# ESP32_with_USBC.net
KiCad netlist of a schematic drawn in Altium Designer
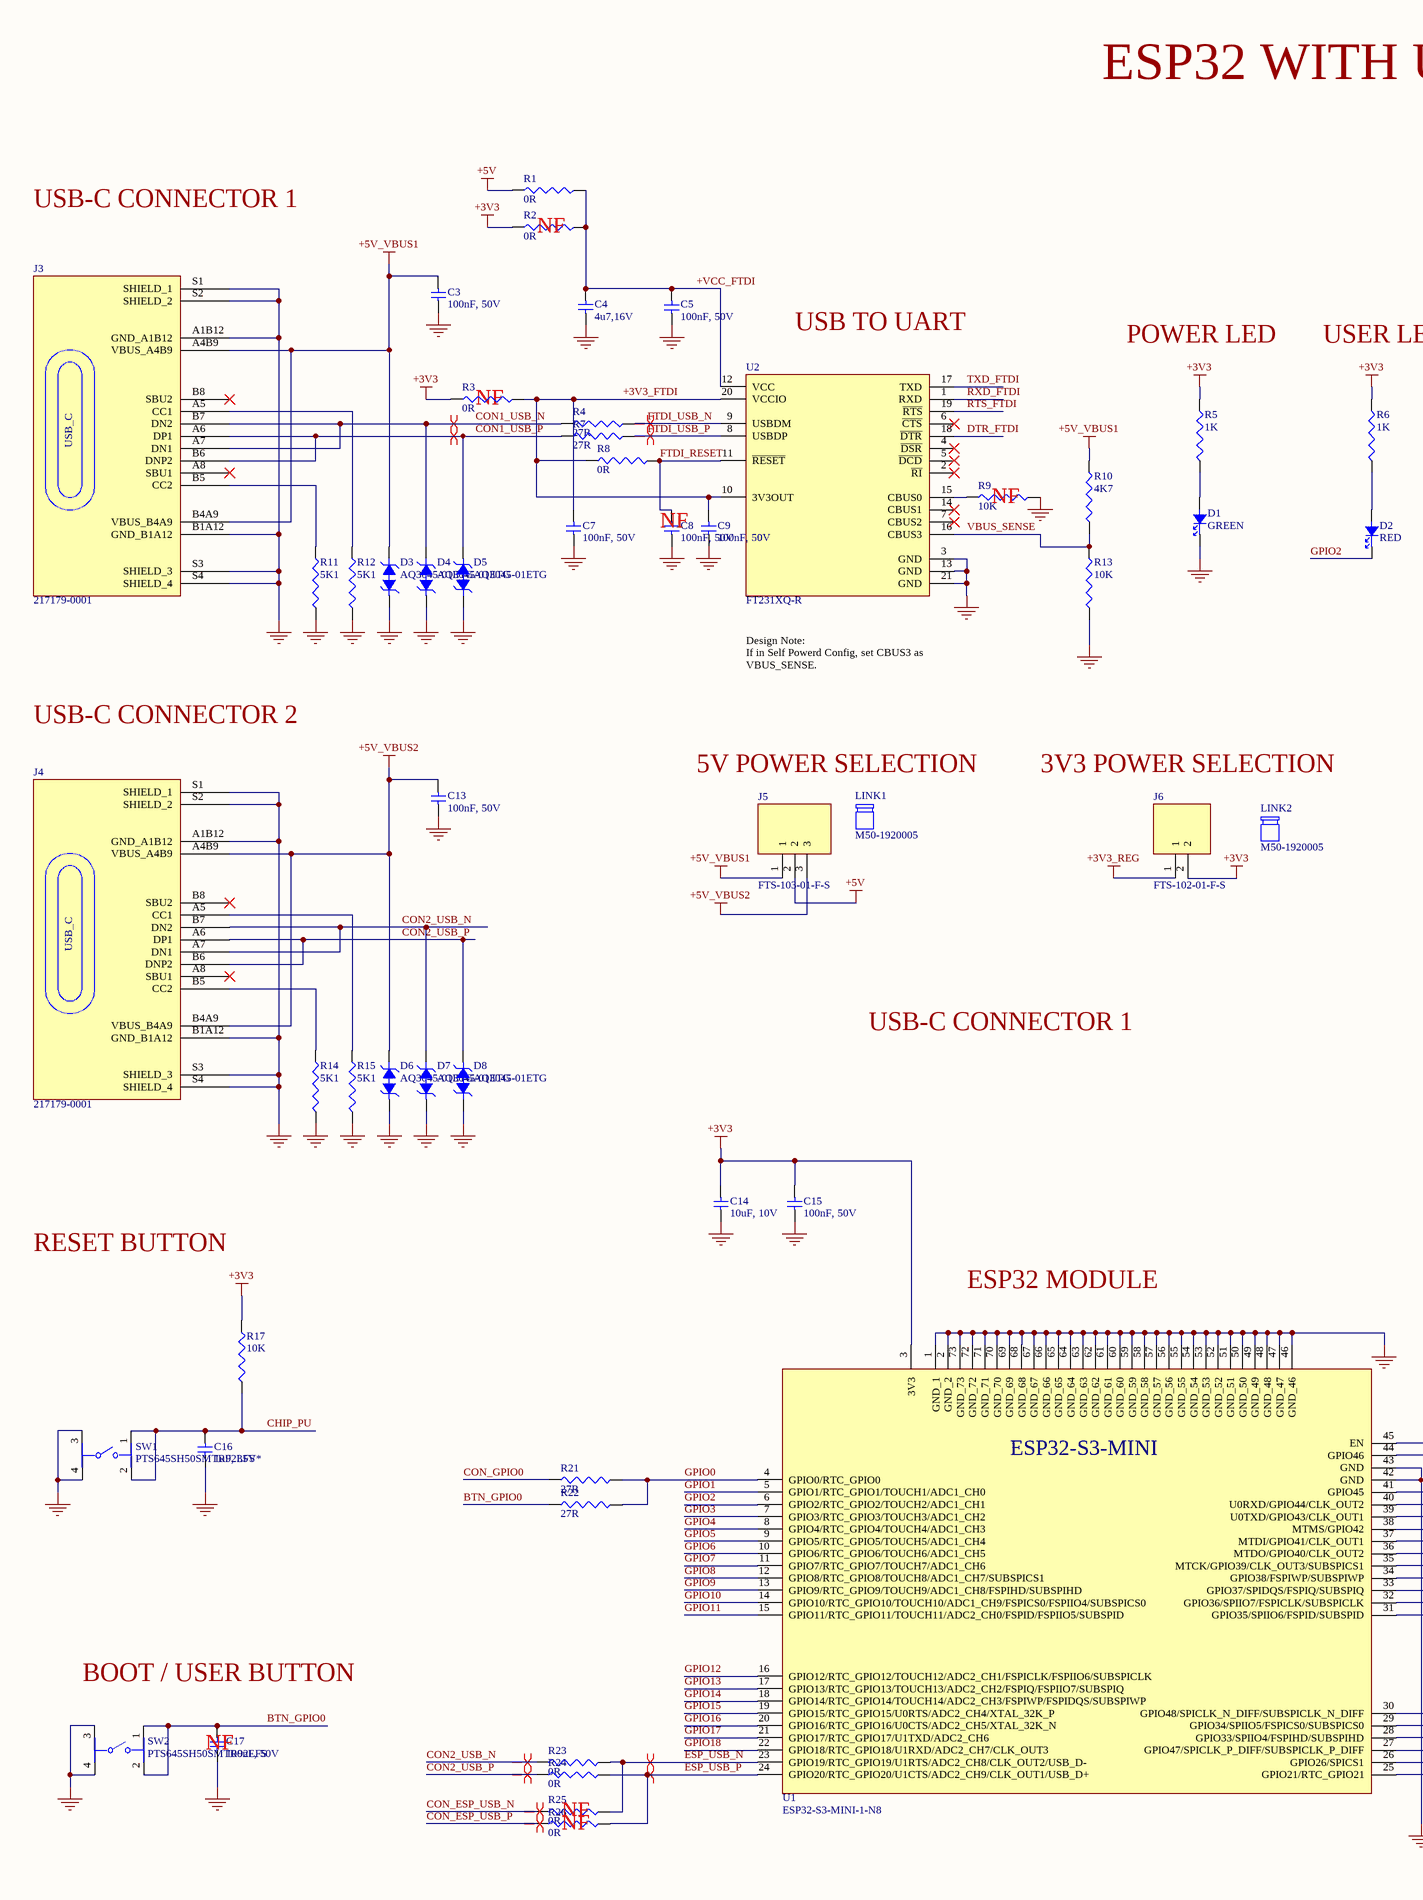
[diagram p0: ESP32 with USBC.SchDoc, left]
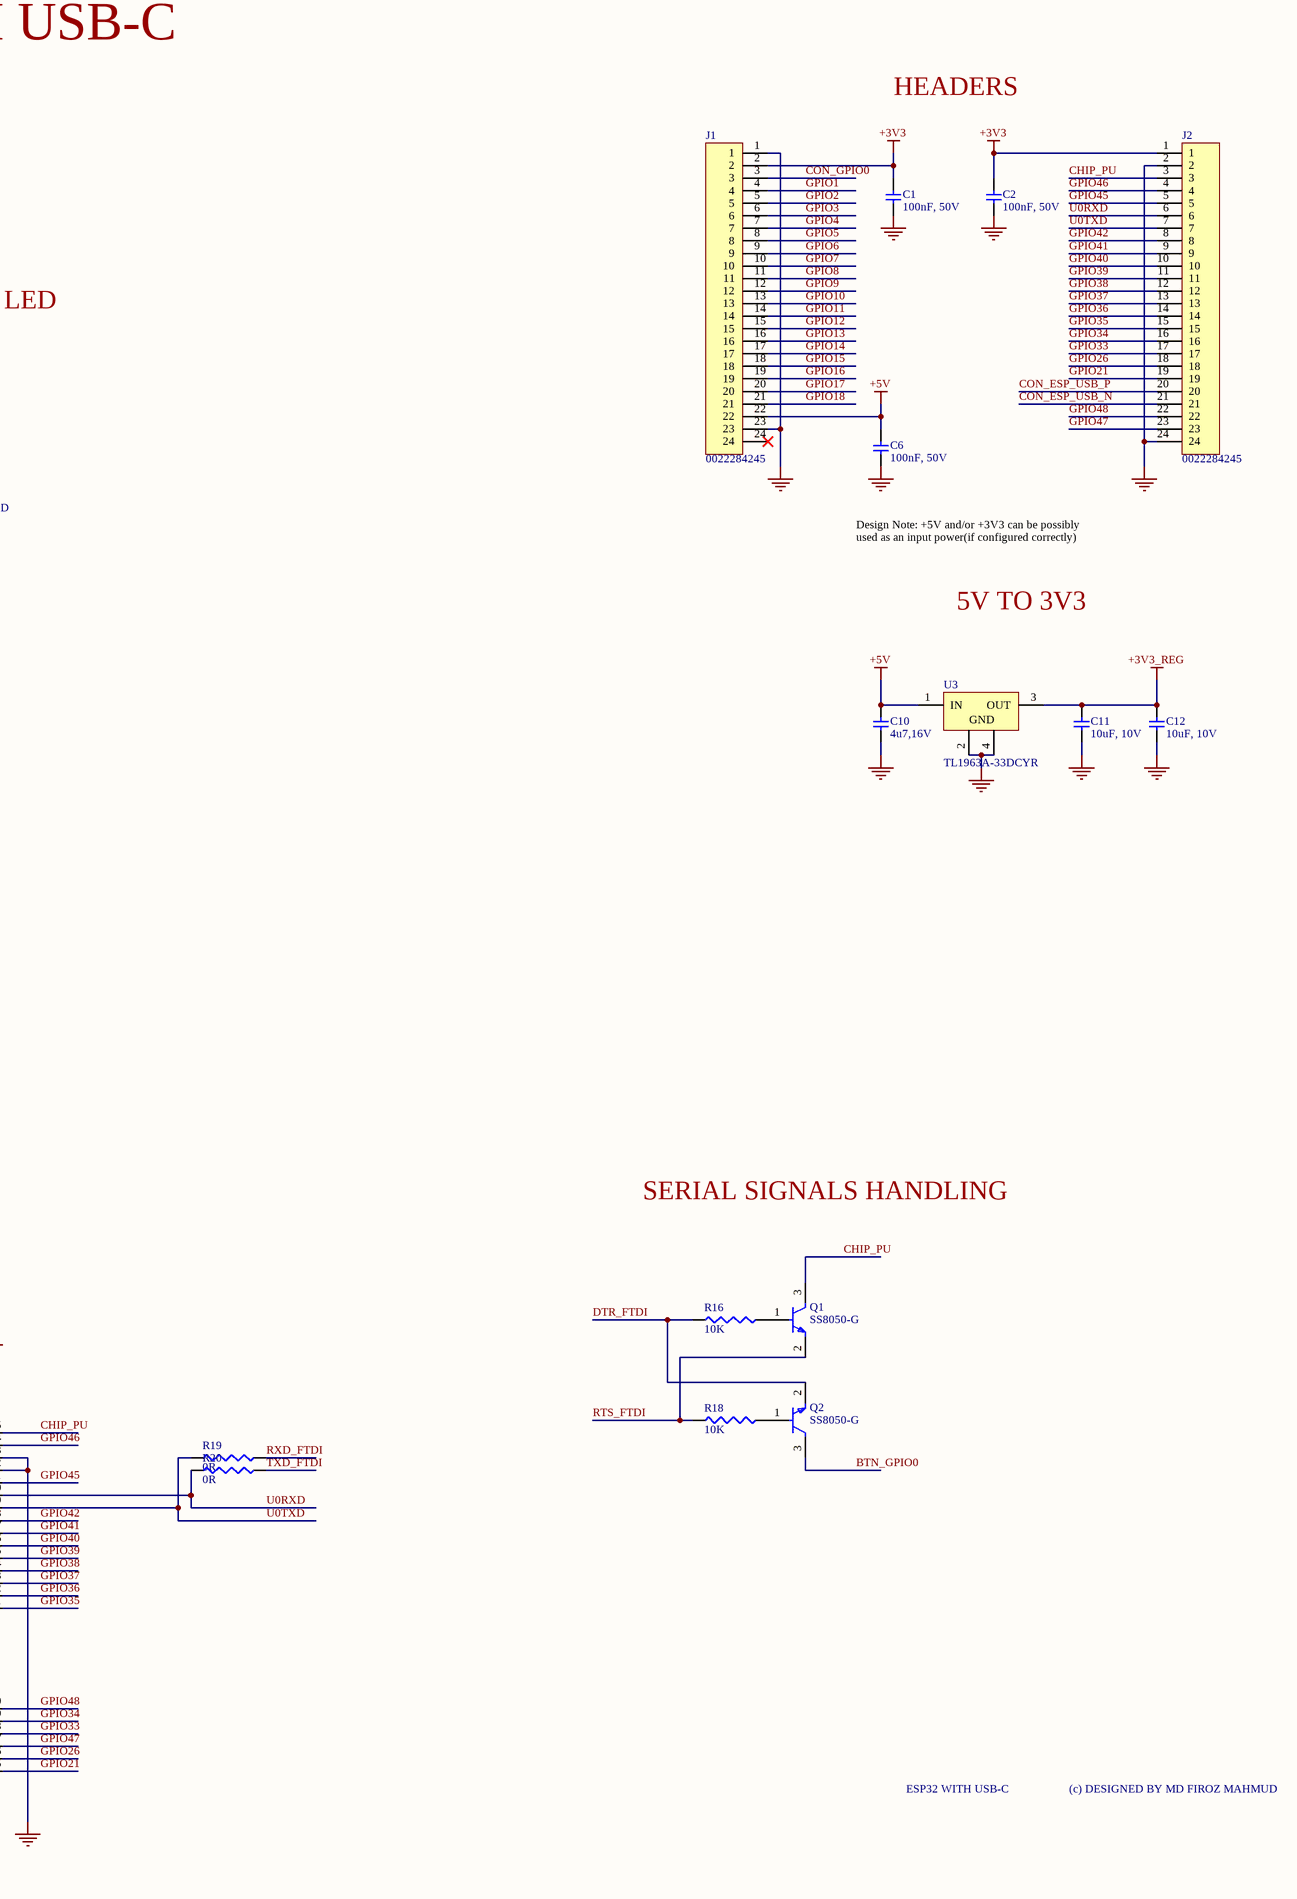
[diagram p1: ESP32 with USBC.SchDoc, right]

(export (version "E")
  (design (tool "Eeschema 10.0.6"))
  (components
    (comp (ref "C1")
      (value "100nF, 50V")
      (footprint "CAPC1005X55N")
      (description "CAP CER 0.1UF 50V X7R 0402")
      (fields
        (field (name "MANUFACTURER") "Samsung")
        (field (name "MANUFACTURER PART NUMBER") "CL05B104KB54PNC")
      )
      (libsource (lib "Schlib") (part "CL05B104KB54PNC"))
    )
    (comp (ref "C2")
      (value "100nF, 50V")
      (footprint "CAPC1005X55N")
      (description "CAP CER 0.1UF 50V X7R 0402")
      (fields
        (field (name "MANUFACTURER") "Samsung")
        (field (name "MANUFACTURER PART NUMBER") "CL05B104KB54PNC")
      )
      (libsource (lib "Schlib") (part "CL05B104KB54PNC"))
    )
    (comp (ref "C3")
      (value "100nF, 50V")
      (footprint "CAPC1005X55N")
      (description "CAP CER 0.1UF 50V X7R 0402")
      (fields
        (field (name "MANUFACTURER") "Samsung")
        (field (name "MANUFACTURER PART NUMBER") "CL05B104KB54PNC")
      )
      (libsource (lib "Schlib") (part "CL05B104KB54PNC"))
    )
    (comp (ref "C4")
      (value "4u7,16V")
      (footprint "CAPC1005X55N")
      (description "CAP CER 4.7UF 16V X5R 0402")
      (fields
        (field (name "MANUFACTURER") "Samsung")
        (field (name "MANUFACTURER PART NUMBER") "CL05A475MO5NUNC")
      )
      (libsource (lib "Schlib") (part "CL05A475MO5NUNC"))
    )
    (comp (ref "C5")
      (value "100nF, 50V")
      (footprint "CAPC1005X55N")
      (description "CAP CER 0.1UF 50V X7R 0402")
      (fields
        (field (name "MANUFACTURER") "Samsung")
        (field (name "MANUFACTURER PART NUMBER") "CL05B104KB54PNC")
      )
      (libsource (lib "Schlib") (part "CL05B104KB54PNC"))
    )
    (comp (ref "C6")
      (value "100nF, 50V")
      (footprint "CAPC1005X55N")
      (description "CAP CER 0.1UF 50V X7R 0402")
      (fields
        (field (name "MANUFACTURER") "Samsung")
        (field (name "MANUFACTURER PART NUMBER") "CL05B104KB54PNC")
      )
      (libsource (lib "Schlib") (part "CL05B104KB54PNC"))
    )
    (comp (ref "C7")
      (value "100nF, 50V")
      (footprint "CAPC1005X55N")
      (description "CAP CER 0.1UF 50V X7R 0402")
      (fields
        (field (name "MANUFACTURER") "Samsung")
        (field (name "MANUFACTURER PART NUMBER") "CL05B104KB54PNC")
      )
      (libsource (lib "Schlib") (part "CL05B104KB54PNC"))
    )
    (comp (ref "C8")
      (value "100nF, 50V")
      (footprint "CAPC1005X55N")
      (description "CAP CER 0.1UF 50V X7R 0402")
      (fields
        (field (name "MANUFACTURER") "Samsung")
        (field (name "MANUFACTURER PART NUMBER") "CL05B104KB54PNC")
      )
      (libsource (lib "Schlib") (part "CL05B104KB54PNC"))
    )
    (comp (ref "C9")
      (value "100nF, 50V")
      (footprint "CAPC1005X55N")
      (description "CAP CER 0.1UF 50V X7R 0402")
      (fields
        (field (name "MANUFACTURER") "Samsung")
        (field (name "MANUFACTURER PART NUMBER") "CL05B104KB54PNC")
      )
      (libsource (lib "Schlib") (part "CL05B104KB54PNC"))
    )
    (comp (ref "C10")
      (value "4u7,16V")
      (footprint "CAPC1005X55N")
      (description "CAP CER 4.7UF 16V X5R 0402")
      (fields
        (field (name "MANUFACTURER") "Samsung")
        (field (name "MANUFACTURER PART NUMBER") "CL05A475MO5NUNC")
      )
      (libsource (lib "Schlib") (part "CL05A475MO5NUNC"))
    )
    (comp (ref "C11")
      (value "10uF, 10V")
      (footprint "CAPC1005X55N")
      (description "CAP CER 10UF 10V X5R 0402")
      (fields
        (field (name "MANUFACTURER") "Samsung")
        (field (name "MANUFACTURER PART NUMBER") "CL05A106MP8NUB8")
      )
      (libsource (lib "Schlib") (part "CL05A106MP8NUB8"))
    )
    (comp (ref "C12")
      (value "10uF, 10V")
      (footprint "CAPC1005X55N")
      (description "CAP CER 10UF 10V X5R 0402")
      (fields
        (field (name "MANUFACTURER") "Samsung")
        (field (name "MANUFACTURER PART NUMBER") "CL05A106MP8NUB8")
      )
      (libsource (lib "Schlib") (part "CL05A106MP8NUB8"))
    )
    (comp (ref "C13")
      (value "100nF, 50V")
      (footprint "CAPC1005X55N")
      (description "CAP CER 0.1UF 50V X7R 0402")
      (fields
        (field (name "MANUFACTURER") "Samsung")
        (field (name "MANUFACTURER PART NUMBER") "CL05B104KB54PNC")
      )
      (libsource (lib "Schlib") (part "CL05B104KB54PNC"))
    )
    (comp (ref "C14")
      (value "10uF, 10V")
      (footprint "CAPC1005X55N")
      (description "CAP CER 10UF 10V X5R 0402")
      (fields
        (field (name "MANUFACTURER") "Samsung")
        (field (name "MANUFACTURER PART NUMBER") "CL05A106MP8NUB8")
      )
      (libsource (lib "Schlib") (part "CL05A106MP8NUB8"))
    )
    (comp (ref "C15")
      (value "100nF, 50V")
      (footprint "CAPC1005X55N")
      (description "CAP CER 0.1UF 50V X7R 0402")
      (fields
        (field (name "MANUFACTURER") "Samsung")
        (field (name "MANUFACTURER PART NUMBER") "CL05B104KB54PNC")
      )
      (libsource (lib "Schlib") (part "CL05B104KB54PNC"))
    )
    (comp (ref "C16")
      (value "1uF, 35V*")
      (footprint "CAPC1005X55N")
      (description "CAP CER 1UF 35V X5R 0402")
      (fields
        (field (name "MANUFACTURER") "Samsung")
        (field (name "MANUFACTURER PART NUMBER") "CL05A105KL5NRNC")
      )
      (libsource (lib "Schlib") (part "CL05A105KL5NRNC"))
    )
    (comp (ref "C17")
      (value "100nF, 50V")
      (footprint "CAPC1005X55N")
      (description "CAP CER 0.1UF 50V X7R 0402")
      (fields
        (field (name "MANUFACTURER") "Samsung")
        (field (name "MANUFACTURER PART NUMBER") "CL05B104KB54PNC")
      )
      (libsource (lib "Schlib") (part "CL05B104KB54PNC"))
    )
    (comp (ref "D1")
      (value "GREEN")
      (footprint "LED0402G")
      (description "LED YLW-GRN 0402 SMD")
      (fields
        (field (name "MANUFACTURER") "Vishay")
        (field (name "MANUFACTURER PART NUMBER") "VLMG1500-GS08")
      )
      (libsource (lib "Schlib") (part "VLMG1500-GS08"))
    )
    (comp (ref "D2")
      (value "RED")
      (footprint "LED0402R")
      (description "LED RED 0402 SMD")
      (fields
        (field (name "MANUFACTURER") "Vishay")
        (field (name "MANUFACTURER PART NUMBER") "VLMS1500-GS08")
      )
      (libsource (lib "Schlib") (part "VLMS1500-GS08"))
    )
    (comp (ref "D3")
      (value "AQ3045-01ETG")
      (footprint "SOD882")
      (description "TVS DIODE 5.3VWM 12VC SOD882")
      (fields (field (name "MANUFACTURER") "Littelfuse") (field (name "LCSC PART NUMBER") "C3710326"))
      (libsource (lib "Schlib") (part "AQ3045-01ETG"))
    )
    (comp (ref "D4")
      (value "AQ3045-01ETG")
      (footprint "SOD882")
      (description "TVS DIODE 5.3VWM 12VC SOD882")
      (fields (field (name "MANUFACTURER") "Littelfuse") (field (name "LCSC PART NUMBER") "C3710326"))
      (libsource (lib "Schlib") (part "AQ3045-01ETG"))
    )
    (comp (ref "D5")
      (value "AQ3045-01ETG")
      (footprint "SOD882")
      (description "TVS DIODE 5.3VWM 12VC SOD882")
      (fields (field (name "MANUFACTURER") "Littelfuse") (field (name "LCSC PART NUMBER") "C3710326"))
      (libsource (lib "Schlib") (part "AQ3045-01ETG"))
    )
    (comp (ref "D6")
      (value "AQ3045-01ETG")
      (footprint "SOD882")
      (description "TVS DIODE 5.3VWM 12VC SOD882")
      (fields (field (name "MANUFACTURER") "Littelfuse") (field (name "LCSC PART NUMBER") "C3710326"))
      (libsource (lib "Schlib") (part "AQ3045-01ETG"))
    )
    (comp (ref "D7")
      (value "AQ3045-01ETG")
      (footprint "SOD882")
      (description "TVS DIODE 5.3VWM 12VC SOD882")
      (fields (field (name "MANUFACTURER") "Littelfuse") (field (name "LCSC PART NUMBER") "C3710326"))
      (libsource (lib "Schlib") (part "AQ3045-01ETG"))
    )
    (comp (ref "D8")
      (value "AQ3045-01ETG")
      (footprint "SOD882")
      (description "TVS DIODE 5.3VWM 12VC SOD882")
      (fields (field (name "MANUFACTURER") "Littelfuse") (field (name "LCSC PART NUMBER") "C3710326"))
      (libsource (lib "Schlib") (part "AQ3045-01ETG"))
    )
    (comp (ref "J1")
      (value "0022284245")
      (footprint "HDR_1X24_2.54MM")
      (description "CONN HEADER VERT 24POS 2.54MM")
      (fields (field (name "MANUFACTURER") "Molex") (field (name "LCSC PART NUMBER") "C7145888"))
      (libsource (lib "") (part "0022284245_1"))
    )
    (comp (ref "J2")
      (value "0022284245")
      (footprint "HDR_1X24_2.54MM")
      (description "CONN HEADER VERT 24POS 2.54MM")
      (fields (field (name "MANUFACTURER") "Molex") (field (name "LCSC PART NUMBER") "C7145888"))
      (libsource (lib "Schlib") (part "0022284245"))
    )
    (comp (ref "J3")
      (value "217179-0001")
      (footprint "FP-2171790001-MFG")
      (description "CONN RCP USB2.0 TYP C 24P SMD RA")
      (fields (field (name "MANUFACTURER") "Molex") (field (name "LCSC PART NUMBER") "C3197684"))
      (libsource (lib "Schlib") (part "217179-0001"))
    )
    (comp (ref "J4")
      (value "217179-0001")
      (footprint "FP-2171790001-MFG")
      (description "CONN RCP USB2.0 TYP C 24P SMD RA")
      (fields (field (name "MANUFACTURER") "Molex") (field (name "LCSC PART NUMBER") "C3197684"))
      (libsource (lib "Schlib") (part "217179-0001"))
    )
    (comp (ref "J5")
      (value "FTS-103-01-F-S")
      (footprint "HDR_1X3_1.27MM")
      (description "CONN HEADER VERT 3POS 1.27MM")
      (fields (field (name "MANUFACTURER") "Samtec") (field (name "LCSC PART NUMBER") "C3333578"))
      (libsource (lib "Schlib") (part "FTS-103-01-F-S"))
    )
    (comp (ref "J6")
      (value "FTS-102-01-F-S")
      (footprint "HDR_1X2_1.27MM")
      (description "CONN HEADER VERT 2POS 1.27MM")
      (fields (field (name "MANUFACTURER") "Samtec") (field (name "LCSC PART NUMBER") "C6045317"))
      (libsource (lib "Schlib") (part "FTS-102-01-F-S"))
    )
    (comp (ref "LINK1")
      (value "M50-1920005")
      (description "CONN SHUNT 1.27MM RED")
      (fields (field (name "MANUFACTURER") "Harwin") (field (name "LCSC PART NUMBER") "C6985646"))
      (libsource (lib "Schlib") (part "M50-1920005"))
    )
    (comp (ref "LINK2")
      (value "M50-1920005")
      (description "CONN SHUNT 1.27MM RED")
      (fields (field (name "MANUFACTURER") "Harwin") (field (name "LCSC PART NUMBER") "C6985646"))
      (libsource (lib "Schlib") (part "M50-1920005"))
    )
    (comp (ref "Q1")
      (value "SS8050-G")
      (footprint "FP-SS8050-G-IPC_B")
      (description "TRANS NPN 25V 1.5A SOT23-3")
      (fields (field (name "MANUFACTURER") "Comchip") (field (name "LCSC PART NUMBER") "C164886"))
      (libsource (lib "Schlib") (part "SS8050-G"))
    )
    (comp (ref "Q2")
      (value "SS8050-G")
      (footprint "FP-SS8050-G-IPC_B")
      (description "TRANS NPN 25V 1.5A SOT23-3")
      (fields (field (name "MANUFACTURER") "Comchip") (field (name "LCSC PART NUMBER") "C164886"))
      (libsource (lib "Schlib") (part "SS8050-G"))
    )
    (comp (ref "R1")
      (value "0R")
      (footprint "RESC1005X37N")
      (description "RES 0 OHM JUMPER 1/16W 0402")
      (fields
        (field (name "MANUFACTURER") "Yageo")
        (field (name "MANUFACTURER PART NUMBER") "RC0402JR-070RL")
      )
      (libsource (lib "Schlib") (part "RC0402JR-070RL"))
    )
    (comp (ref "R2")
      (value "0R")
      (footprint "RESC1005X37N")
      (description "RES 0 OHM JUMPER 1/16W 0402")
      (fields
        (field (name "MANUFACTURER") "Yageo")
        (field (name "MANUFACTURER PART NUMBER") "RC0402JR-070RL")
      )
      (libsource (lib "Schlib") (part "RC0402JR-070RL"))
    )
    (comp (ref "R3")
      (value "0R")
      (footprint "RESC1005X37N")
      (description "RES 0 OHM JUMPER 1/16W 0402")
      (fields
        (field (name "MANUFACTURER") "Yageo")
        (field (name "MANUFACTURER PART NUMBER") "RC0402JR-070RL")
      )
      (libsource (lib "Schlib") (part "RC0402JR-070RL"))
    )
    (comp (ref "R4")
      (value "27R")
      (footprint "RESC1005X37N")
      (description "RES 27 OHM 1% 1/16W 0402")
      (fields
        (field (name "MANUFACTURER") "Yageo")
        (field (name "MANUFACTURER PART NUMBER") "RC0402FR-0727RL")
      )
      (libsource (lib "Schlib") (part "RC0402FR-0727RL"))
    )
    (comp (ref "R5")
      (value "1K")
      (footprint "RESC1005X37N")
      (description "RES 1K OHM 1% 1/16W 0402")
      (fields
        (field (name "MANUFACTURER") "Yageo")
        (field (name "MANUFACTURER PART NUMBER") "RC0402FR-071KL")
      )
      (libsource (lib "Schlib") (part "RC0402FR-071KL"))
    )
    (comp (ref "R6")
      (value "1K")
      (footprint "RESC1005X37N")
      (description "RES 1K OHM 1% 1/16W 0402")
      (fields
        (field (name "MANUFACTURER") "Yageo")
        (field (name "MANUFACTURER PART NUMBER") "RC0402FR-071KL")
      )
      (libsource (lib "Schlib") (part "RC0402FR-071KL"))
    )
    (comp (ref "R7")
      (value "27R")
      (footprint "RESC1005X37N")
      (description "RES 27 OHM 1% 1/16W 0402")
      (fields
        (field (name "MANUFACTURER") "Yageo")
        (field (name "MANUFACTURER PART NUMBER") "RC0402FR-0727RL")
      )
      (libsource (lib "Schlib") (part "RC0402FR-0727RL"))
    )
    (comp (ref "R8")
      (value "0R")
      (footprint "RESC1005X37N")
      (description "RES 0 OHM JUMPER 1/16W 0402")
      (fields
        (field (name "MANUFACTURER") "Yageo")
        (field (name "MANUFACTURER PART NUMBER") "RC0402JR-070RL")
      )
      (libsource (lib "Schlib") (part "RC0402JR-070RL"))
    )
    (comp (ref "R9")
      (value "10K")
      (footprint "RESC1005X37N")
      (description "RES SMD 10K OHM 1% 1/16W 0402")
      (fields
        (field (name "MANUFACTURER") "Yageo")
        (field (name "MANUFACTURER PART NUMBER") "AC0402FR-0710KL")
      )
      (libsource (lib "Schlib") (part "AC0402FR-0710KL"))
    )
    (comp (ref "R10")
      (value "4K7")
      (footprint "RESC1005X37N")
      (description "RES 4.7K OHM 1% 1/16W 0402")
      (fields
        (field (name "MANUFACTURER") "Yageo")
        (field (name "MANUFACTURER PART NUMBER") "RC0402FR-074K7L")
      )
      (libsource (lib "Schlib") (part "RC0402FR-074K7L"))
    )
    (comp (ref "R11")
      (value "5K1")
      (footprint "RESC1005X37N")
      (description "RES SMD 5.1K OHM 1% 1/16W 0402")
      (fields
        (field (name "MANUFACTURER") "Yageo")
        (field (name "MANUFACTURER PART NUMBER") "AC0402FR-075K1L")
      )
      (libsource (lib "Schlib") (part "AC0402FR-075K1L"))
    )
    (comp (ref "R12")
      (value "5K1")
      (footprint "RESC1005X37N")
      (description "RES SMD 5.1K OHM 1% 1/16W 0402")
      (fields
        (field (name "MANUFACTURER") "Yageo")
        (field (name "MANUFACTURER PART NUMBER") "AC0402FR-075K1L")
      )
      (libsource (lib "Schlib") (part "AC0402FR-075K1L"))
    )
    (comp (ref "R13")
      (value "10K")
      (footprint "RESC1005X37N")
      (description "RES SMD 10K OHM 1% 1/16W 0402")
      (fields
        (field (name "MANUFACTURER") "Yageo")
        (field (name "MANUFACTURER PART NUMBER") "AC0402FR-0710KL")
      )
      (libsource (lib "Schlib") (part "AC0402FR-0710KL"))
    )
    (comp (ref "R14")
      (value "5K1")
      (footprint "RESC1005X37N")
      (description "RES SMD 5.1K OHM 1% 1/16W 0402")
      (fields
        (field (name "MANUFACTURER") "Yageo")
        (field (name "MANUFACTURER PART NUMBER") "AC0402FR-075K1L")
      )
      (libsource (lib "Schlib") (part "AC0402FR-075K1L"))
    )
    (comp (ref "R15")
      (value "5K1")
      (footprint "RESC1005X37N")
      (description "RES SMD 5.1K OHM 1% 1/16W 0402")
      (fields
        (field (name "MANUFACTURER") "Yageo")
        (field (name "MANUFACTURER PART NUMBER") "AC0402FR-075K1L")
      )
      (libsource (lib "Schlib") (part "AC0402FR-075K1L"))
    )
    (comp (ref "R16")
      (value "10K")
      (footprint "RESC1005X37N")
      (description "RES SMD 10K OHM 1% 1/16W 0402")
      (fields
        (field (name "MANUFACTURER") "Yageo")
        (field (name "MANUFACTURER PART NUMBER") "AC0402FR-0710KL")
      )
      (libsource (lib "Schlib") (part "AC0402FR-0710KL"))
    )
    (comp (ref "R17")
      (value "10K")
      (footprint "RESC1005X37N")
      (description "RES SMD 10K OHM 1% 1/16W 0402")
      (fields
        (field (name "MANUFACTURER") "Yageo")
        (field (name "MANUFACTURER PART NUMBER") "AC0402FR-0710KL")
      )
      (libsource (lib "Schlib") (part "AC0402FR-0710KL"))
    )
    (comp (ref "R18")
      (value "10K")
      (footprint "RESC1005X37N")
      (description "RES SMD 10K OHM 1% 1/16W 0402")
      (fields
        (field (name "MANUFACTURER") "Yageo")
        (field (name "MANUFACTURER PART NUMBER") "AC0402FR-0710KL")
      )
      (libsource (lib "Schlib") (part "AC0402FR-0710KL"))
    )
    (comp (ref "R19")
      (value "0R")
      (footprint "RESC1005X37N")
      (description "RES 0 OHM JUMPER 1/16W 0402")
      (fields
        (field (name "MANUFACTURER") "Yageo")
        (field (name "MANUFACTURER PART NUMBER") "RC0402JR-070RL")
      )
      (libsource (lib "Schlib") (part "RC0402JR-070RL"))
    )
    (comp (ref "R20")
      (value "0R")
      (footprint "RESC1005X37N")
      (description "RES 0 OHM JUMPER 1/16W 0402")
      (fields
        (field (name "MANUFACTURER") "Yageo")
        (field (name "MANUFACTURER PART NUMBER") "RC0402JR-070RL")
      )
      (libsource (lib "Schlib") (part "RC0402JR-070RL"))
    )
    (comp (ref "R21")
      (value "27R")
      (footprint "RESC1005X37N")
      (description "RES 27 OHM 1% 1/16W 0402")
      (fields
        (field (name "MANUFACTURER") "Yageo")
        (field (name "MANUFACTURER PART NUMBER") "RC0402FR-0727RL")
      )
      (libsource (lib "Schlib") (part "RC0402FR-0727RL"))
    )
    (comp (ref "R22")
      (value "27R")
      (footprint "RESC1005X37N")
      (description "RES 27 OHM 1% 1/16W 0402")
      (fields
        (field (name "MANUFACTURER") "Yageo")
        (field (name "MANUFACTURER PART NUMBER") "RC0402FR-0727RL")
      )
      (libsource (lib "Schlib") (part "RC0402FR-0727RL"))
    )
    (comp (ref "R23")
      (value "0R")
      (footprint "RESC1005X37N")
      (description "RES 0 OHM JUMPER 1/16W 0402")
      (fields
        (field (name "MANUFACTURER") "Yageo")
        (field (name "MANUFACTURER PART NUMBER") "RC0402JR-070RL")
      )
      (libsource (lib "Schlib") (part "RC0402JR-070RL"))
    )
    (comp (ref "R24")
      (value "0R")
      (footprint "RESC1005X37N")
      (description "RES 0 OHM JUMPER 1/16W 0402")
      (fields
        (field (name "MANUFACTURER") "Yageo")
        (field (name "MANUFACTURER PART NUMBER") "RC0402JR-070RL")
      )
      (libsource (lib "Schlib") (part "RC0402JR-070RL"))
    )
    (comp (ref "R25")
      (value "0R")
      (footprint "RESC1005X37N")
      (description "RES 0 OHM JUMPER 1/16W 0402")
      (fields
        (field (name "MANUFACTURER") "Yageo")
        (field (name "MANUFACTURER PART NUMBER") "RC0402JR-070RL")
      )
      (libsource (lib "Schlib") (part "RC0402JR-070RL"))
    )
    (comp (ref "R26")
      (value "0R")
      (footprint "RESC1005X37N")
      (description "RES 0 OHM JUMPER 1/16W 0402")
      (fields
        (field (name "MANUFACTURER") "Yageo")
        (field (name "MANUFACTURER PART NUMBER") "RC0402JR-070RL")
      )
      (libsource (lib "Schlib") (part "RC0402JR-070RL"))
    )
    (comp (ref "SW1")
      (value "PTS645SH50SMTR92LFS")
      (footprint "FP-PTS645SH50SMTR92LFS-MFG")
      (description "SWITCH TACTILE SPST-NO 0.05A 12V")
      (fields (field (name "MANUFACTURER") "ITT C&K") (field (name "LCSC PART NUMBER") "C221869"))
      (libsource (lib "Schlib") (part "PTS645SH50SMTR92LFS"))
    )
    (comp (ref "SW2")
      (value "PTS645SH50SMTR92LFS")
      (footprint "FP-PTS645SH50SMTR92LFS-MFG")
      (description "SWITCH TACTILE SPST-NO 0.05A 12V")
      (fields (field (name "MANUFACTURER") "ITT C&K") (field (name "LCSC PART NUMBER") "C221869"))
      (libsource (lib "Schlib") (part "PTS645SH50SMTR92LFS"))
    )
    (comp (ref "U1")
      (value "ESP32-S3-MINI-1-N8")
      (footprint "XCVR_ESP32-S3-MINI-1-N8")
      (description "SMD module, ESP32-S3FN8, 8 MB SPI flash, PCB antenna")
      (fields (field (name "MANUFACTURER") "Espressif Systems") (field (name "LCSC PART NUMBER") "C2913206"))
      (libsource (lib "Schlib") (part "ESP32-S3-MINI-1-N8"))
    )
    (comp (ref "U2")
      (value "FT231XQ-R")
      (footprint "FP-QFN-20-IPC_B")
      (description "IC USB SERIAL FULL UART 20QFN")
      (fields (field (name "MANUFACTURER") "FTDI") (field (name "LCSC PART NUMBER") "C132159"))
      (libsource (lib "Schlib") (part "FT231XQ-R"))
    )
    (comp (ref "U3")
      (value "TL1963A-33DCYR")
      (footprint "DCY0004A_N")
      (description "IC REG LINEAR 3.3V 1.5A SOT223-4")
      (fields (field (name "MANUFACTURER") "Texas Instruments") (field (name "LCSC PART NUMBER") "C181262"))
      (libsource (lib "Schlib") (part "TL1963A-33DCYR"))
    )
  )
  (nets
    (net (code "1") (name "+3V3") (class "Default")
      (node (ref "C1") (pin "2") (pinfunction "2_2") (pintype "passive"))
      (node (ref "C14") (pin "2") (pinfunction "2_2") (pintype "passive"))
      (node (ref "C15") (pin "2") (pinfunction "2_2") (pintype "passive"))
      (node (ref "C2") (pin "2") (pinfunction "2_2") (pintype "passive"))
      (node (ref "J1") (pin "2") (pinfunction "2_2") (pintype "passive"))
      (node (ref "J2") (pin "1") (pinfunction "1_1") (pintype "passive"))
      (node (ref "J6") (pin "2") (pinfunction "2_2") (pintype "passive"))
      (node (ref "R17") (pin "2") (pinfunction "2_2") (pintype "passive"))
      (node (ref "R2") (pin "1") (pinfunction "1_1") (pintype "passive"))
      (node (ref "R3") (pin "1") (pinfunction "1_1") (pintype "passive"))
      (node (ref "R5") (pin "2") (pinfunction "2_2") (pintype "passive"))
      (node (ref "R6") (pin "2") (pinfunction "2_2") (pintype "passive"))
      (node (ref "U1") (pin "3") (pinfunction "3V3_3") (pintype "passive"))
    )
    (net (code "2") (name "+3V3_REG") (class "Default")
      (node (ref "C11") (pin "2") (pinfunction "2_2") (pintype "passive"))
      (node (ref "C12") (pin "2") (pinfunction "2_2") (pintype "passive"))
      (node (ref "J6") (pin "1") (pinfunction "1_1") (pintype "passive"))
      (node (ref "U3") (pin "3") (pinfunction "OUT_3") (pintype "power_in"))
    )
    (net (code "3") (name "+5V") (class "Default")
      (node (ref "C10") (pin "1") (pinfunction "1_1") (pintype "passive"))
      (node (ref "C6") (pin "2") (pinfunction "2_2") (pintype "passive"))
      (node (ref "J1") (pin "22") (pinfunction "22_22") (pintype "passive"))
      (node (ref "J5") (pin "2") (pinfunction "2_2") (pintype "passive"))
      (node (ref "R1") (pin "1") (pinfunction "1_1") (pintype "passive"))
      (node (ref "U3") (pin "1") (pinfunction "IN_1") (pintype "power_in"))
    )
    (net (code "4") (name "+5V_VBUS1") (class "Default")
      (node (ref "C3") (pin "2") (pinfunction "2_2") (pintype "passive"))
      (node (ref "D3") (pin "2") (pinfunction "2_2") (pintype "passive"))
      (node (ref "J3") (pin "A4B9") (pinfunction "VBUS_A4B9_A4B9") (pintype "passive"))
      (node (ref "J3") (pin "B4A9") (pinfunction "VBUS_B4A9_B4A9") (pintype "passive"))
      (node (ref "J5") (pin "1") (pinfunction "1_1") (pintype "passive"))
      (node (ref "R10") (pin "2") (pinfunction "2_2") (pintype "passive"))
    )
    (net (code "5") (name "+5V_VBUS2") (class "Default")
      (node (ref "C13") (pin "2") (pinfunction "2_2") (pintype "passive"))
      (node (ref "D6") (pin "2") (pinfunction "2_2") (pintype "passive"))
      (node (ref "J4") (pin "A4B9") (pinfunction "VBUS_A4B9_A4B9") (pintype "passive"))
      (node (ref "J4") (pin "B4A9") (pinfunction "VBUS_B4A9_B4A9") (pintype "passive"))
      (node (ref "J5") (pin "3") (pinfunction "3_3") (pintype "passive"))
    )
    (net (code "6") (name "/+3V3_FTDI") (class "Default")
      (node (ref "C7") (pin "2") (pinfunction "2_2") (pintype "passive"))
      (node (ref "C9") (pin "2") (pinfunction "2_2") (pintype "passive"))
      (node (ref "R3") (pin "2") (pinfunction "2_2") (pintype "passive"))
      (node (ref "R8") (pin "1") (pinfunction "1_1") (pintype "passive"))
      (node (ref "U2") (pin "10") (pinfunction "3V3OUT_10") (pintype "passive"))
      (node (ref "U2") (pin "20") (pinfunction "VCCIO_20") (pintype "passive"))
    )
    (net (code "7") (name "/+VCC_FTDI") (class "Default")
      (node (ref "C4") (pin "1") (pinfunction "1_1") (pintype "passive"))
      (node (ref "C5") (pin "2") (pinfunction "2_2") (pintype "passive"))
      (node (ref "R1") (pin "2") (pinfunction "2_2") (pintype "passive"))
      (node (ref "R2") (pin "2") (pinfunction "2_2") (pintype "passive"))
      (node (ref "U2") (pin "12") (pinfunction "VCC_12") (pintype "passive"))
    )
    (net (code "8") (name "/BTN_GPIO0") (class "Default")
      (node (ref "C17") (pin "2") (pinfunction "2_2") (pintype "passive"))
      (node (ref "Q2") (pin "3") (pinfunction "C_3") (pintype "passive"))
      (node (ref "R22") (pin "1") (pinfunction "1_1") (pintype "passive"))
      (node (ref "SW2") (pin "1") (pinfunction "1_1") (pintype "passive"))
      (node (ref "SW2") (pin "2") (pinfunction "2_2") (pintype "passive"))
    )
    (net (code "9") (name "/CHIP_PU") (class "Default")
      (node (ref "C16") (pin "2") (pinfunction "2_2") (pintype "passive"))
      (node (ref "J2") (pin "3") (pinfunction "3_3") (pintype "passive"))
      (node (ref "Q1") (pin "3") (pinfunction "C_3") (pintype "passive"))
      (node (ref "R17") (pin "1") (pinfunction "1_1") (pintype "passive"))
      (node (ref "SW1") (pin "1") (pinfunction "1_1") (pintype "passive"))
      (node (ref "SW1") (pin "2") (pinfunction "2_2") (pintype "passive"))
      (node (ref "U1") (pin "45") (pinfunction "EN_45") (pintype "passive"))
    )
    (net (code "10") (name "/CON1_USB_N") (class "Default")
      (node (ref "D4") (pin "2") (pinfunction "2_2") (pintype "passive"))
      (node (ref "J3") (pin "A7") (pinfunction "DN1_A7") (pintype "passive"))
      (node (ref "J3") (pin "B7") (pinfunction "DN2_B7") (pintype "passive"))
      (node (ref "R4") (pin "1") (pinfunction "1_1") (pintype "passive"))
    )
    (net (code "11") (name "/CON1_USB_P") (class "Default")
      (node (ref "D5") (pin "1") (pinfunction "1_1") (pintype "passive"))
      (node (ref "J3") (pin "A6") (pinfunction "DP1_A6") (pintype "passive"))
      (node (ref "J3") (pin "B6") (pinfunction "DNP2_B6") (pintype "passive"))
      (node (ref "R7") (pin "1") (pinfunction "1_1") (pintype "passive"))
    )
    (net (code "12") (name "/CON2_USB_N") (class "Default")
      (node (ref "D7") (pin "2") (pinfunction "2_2") (pintype "passive"))
      (node (ref "J4") (pin "A7") (pinfunction "DN1_A7") (pintype "passive"))
      (node (ref "J4") (pin "B7") (pinfunction "DN2_B7") (pintype "passive"))
      (node (ref "R23") (pin "1") (pinfunction "1_1") (pintype "passive"))
    )
    (net (code "13") (name "/CON2_USB_P") (class "Default")
      (node (ref "D8") (pin "1") (pinfunction "1_1") (pintype "passive"))
      (node (ref "J4") (pin "A6") (pinfunction "DP1_A6") (pintype "passive"))
      (node (ref "J4") (pin "B6") (pinfunction "DNP2_B6") (pintype "passive"))
      (node (ref "R24") (pin "1") (pinfunction "1_1") (pintype "passive"))
    )
    (net (code "14") (name "/CON_ESP_USB_N") (class "Default")
      (node (ref "J2") (pin "21") (pinfunction "21_21") (pintype "passive"))
      (node (ref "R25") (pin "1") (pinfunction "1_1") (pintype "passive"))
    )
    (net (code "15") (name "/CON_ESP_USB_P") (class "Default")
      (node (ref "J2") (pin "20") (pinfunction "20_20") (pintype "passive"))
      (node (ref "R26") (pin "1") (pinfunction "1_1") (pintype "passive"))
    )
    (net (code "16") (name "/CON_GPIO0") (class "Default")
      (node (ref "J1") (pin "3") (pinfunction "3_3") (pintype "passive"))
      (node (ref "R21") (pin "1") (pinfunction "1_1") (pintype "passive"))
    )
    (net (code "17") (name "/DTR_FTDI") (class "Default")
      (node (ref "Q2") (pin "2") (pinfunction "E_2") (pintype "passive"))
      (node (ref "R16") (pin "2") (pinfunction "2_2") (pintype "passive"))
      (node (ref "U2") (pin "18") (pinfunction "~{DTR}_18") (pintype "passive"))
    )
    (net (code "18") (name "/ESP_USB_N") (class "Default")
      (node (ref "R23") (pin "2") (pinfunction "2_2") (pintype "passive"))
      (node (ref "R25") (pin "2") (pinfunction "2_2") (pintype "passive"))
      (node (ref "U1") (pin "23") (pinfunction "GPIO19/RTC_GPIO19/U1RTS/ADC2_CH8/CLK_OUT2/USB_D-_23") (pintype "passive"))
    )
    (net (code "19") (name "/ESP_USB_P") (class "Default")
      (node (ref "R24") (pin "2") (pinfunction "2_2") (pintype "passive"))
      (node (ref "R26") (pin "2") (pinfunction "2_2") (pintype "passive"))
      (node (ref "U1") (pin "24") (pinfunction "GPIO20/RTC_GPIO20/U1CTS/ADC2_CH9/CLK_OUT1/USB_D+_24") (pintype "passive"))
    )
    (net (code "20") (name "/FTDI_RESET") (class "Default")
      (node (ref "C8") (pin "2") (pinfunction "2_2") (pintype "passive"))
      (node (ref "R8") (pin "2") (pinfunction "2_2") (pintype "passive"))
      (node (ref "U2") (pin "11") (pinfunction "~{RESET}_11") (pintype "passive"))
    )
    (net (code "21") (name "/FTDI_USB_N") (class "Default")
      (node (ref "R4") (pin "2") (pinfunction "2_2") (pintype "passive"))
      (node (ref "U2") (pin "9") (pinfunction "USBDM_9") (pintype "passive"))
    )
    (net (code "22") (name "/FTDI_USB_P") (class "Default")
      (node (ref "R7") (pin "2") (pinfunction "2_2") (pintype "passive"))
      (node (ref "U2") (pin "8") (pinfunction "USBDP_8") (pintype "passive"))
    )
    (net (code "23") (name "/GPIO0") (class "Default")
      (node (ref "R21") (pin "2") (pinfunction "2_2") (pintype "passive"))
      (node (ref "R22") (pin "2") (pinfunction "2_2") (pintype "passive"))
      (node (ref "U1") (pin "4") (pinfunction "GPIO0/RTC_GPIO0_4") (pintype "passive"))
    )
    (net (code "24") (name "/GPIO1") (class "Default")
      (node (ref "J1") (pin "4") (pinfunction "4_4") (pintype "passive"))
      (node (ref "U1") (pin "5") (pinfunction "GPIO1/RTC_GPIO1/TOUCH1/ADC1_CH0_5") (pintype "passive"))
    )
    (net (code "25") (name "/GPIO2") (class "Default")
      (node (ref "D2") (pin "1") (pinfunction "1_1") (pintype "passive"))
      (node (ref "J1") (pin "5") (pinfunction "5_5") (pintype "passive"))
      (node (ref "U1") (pin "6") (pinfunction "GPIO2/RTC_GPIO2/TOUCH2/ADC1_CH1_6") (pintype "passive"))
    )
    (net (code "26") (name "/GPIO3") (class "Default")
      (node (ref "J1") (pin "6") (pinfunction "6_6") (pintype "passive"))
      (node (ref "U1") (pin "7") (pinfunction "GPIO3/RTC_GPIO3/TOUCH3/ADC1_CH2_7") (pintype "passive"))
    )
    (net (code "27") (name "/GPIO4") (class "Default")
      (node (ref "J1") (pin "7") (pinfunction "7_7") (pintype "passive"))
      (node (ref "U1") (pin "8") (pinfunction "GPIO4/RTC_GPIO4/TOUCH4/ADC1_CH3_8") (pintype "passive"))
    )
    (net (code "28") (name "/GPIO5") (class "Default")
      (node (ref "J1") (pin "8") (pinfunction "8_8") (pintype "passive"))
      (node (ref "U1") (pin "9") (pinfunction "GPIO5/RTC_GPIO5/TOUCH5/ADC1_CH4_9") (pintype "passive"))
    )
    (net (code "29") (name "/GPIO6") (class "Default")
      (node (ref "J1") (pin "9") (pinfunction "9_9") (pintype "passive"))
      (node (ref "U1") (pin "10") (pinfunction "GPIO6/RTC_GPIO6/TOUCH6/ADC1_CH5_10") (pintype "passive"))
    )
    (net (code "30") (name "/GPIO7") (class "Default")
      (node (ref "J1") (pin "10") (pinfunction "10_10") (pintype "passive"))
      (node (ref "U1") (pin "11") (pinfunction "GPIO7/RTC_GPIO7/TOUCH7/ADC1_CH6_11") (pintype "passive"))
    )
    (net (code "31") (name "/GPIO8") (class "Default")
      (node (ref "J1") (pin "11") (pinfunction "11_11") (pintype "passive"))
      (node (ref "U1") (pin "12") (pinfunction "GPIO8/RTC_GPIO8/TOUCH8/ADC1_CH7/SUBSPICS1_12") (pintype "passive"))
    )
    (net (code "32") (name "/GPIO9") (class "Default")
      (node (ref "J1") (pin "12") (pinfunction "12_12") (pintype "passive"))
      (node (ref "U1") (pin "13") (pinfunction "GPIO9/RTC_GPIO9/TOUCH9/ADC1_CH8/FSPIHD/SUBSPIHD_13") (pintype "passive"))
    )
    (net (code "33") (name "/GPIO10") (class "Default")
      (node (ref "J1") (pin "13") (pinfunction "13_13") (pintype "passive"))
      (node (ref "U1") (pin "14") (pinfunction "GPIO10/RTC_GPIO10/TOUCH10/ADC1_CH9/FSPICS0/FSPIIO4/SUBSPICS0_14") (pintype "passive"))
    )
    (net (code "34") (name "/GPIO11") (class "Default")
      (node (ref "J1") (pin "14") (pinfunction "14_14") (pintype "passive"))
      (node (ref "U1") (pin "15") (pinfunction "GPIO11/RTC_GPIO11/TOUCH11/ADC2_CH0/FSPID/FSPIIO5/SUBSPID_15") (pintype "passive"))
    )
    (net (code "35") (name "/GPIO12") (class "Default")
      (node (ref "J1") (pin "15") (pinfunction "15_15") (pintype "passive"))
      (node (ref "U1") (pin "16") (pinfunction "GPIO12/RTC_GPIO12/TOUCH12/ADC2_CH1/FSPICLK/FSPIIO6/SUBSPICLK_16") (pintype "passive"))
    )
    (net (code "36") (name "/GPIO13") (class "Default")
      (node (ref "J1") (pin "16") (pinfunction "16_16") (pintype "passive"))
      (node (ref "U1") (pin "17") (pinfunction "GPIO13/RTC_GPIO13/TOUCH13/ADC2_CH2/FSPIQ/FSPIIO7/SUBSPIQ_17") (pintype "passive"))
    )
    (net (code "37") (name "/GPIO14") (class "Default")
      (node (ref "J1") (pin "17") (pinfunction "17_17") (pintype "passive"))
      (node (ref "U1") (pin "18") (pinfunction "GPIO14/RTC_GPIO14/TOUCH14/ADC2_CH3/FSPIWP/FSPIDQS/SUBSPIWP_18") (pintype "passive"))
    )
    (net (code "38") (name "/GPIO15") (class "Default")
      (node (ref "J1") (pin "18") (pinfunction "18_18") (pintype "passive"))
      (node (ref "U1") (pin "19") (pinfunction "GPIO15/RTC_GPIO15/U0RTS/ADC2_CH4/XTAL_32K_P_19") (pintype "passive"))
    )
    (net (code "39") (name "/GPIO16") (class "Default")
      (node (ref "J1") (pin "19") (pinfunction "19_19") (pintype "passive"))
      (node (ref "U1") (pin "20") (pinfunction "GPIO16/RTC_GPIO16/U0CTS/ADC2_CH5/XTAL_32K_N_20") (pintype "passive"))
    )
    (net (code "40") (name "/GPIO17") (class "Default")
      (node (ref "J1") (pin "20") (pinfunction "20_20") (pintype "passive"))
      (node (ref "U1") (pin "21") (pinfunction "GPIO17/RTC_GPIO17/U1TXD/ADC2_CH6_21") (pintype "passive"))
    )
    (net (code "41") (name "/GPIO18") (class "Default")
      (node (ref "J1") (pin "21") (pinfunction "21_21") (pintype "passive"))
      (node (ref "U1") (pin "22") (pinfunction "GPIO18/RTC_GPIO18/U1RXD/ADC2_CH7/CLK_OUT3_22") (pintype "passive"))
    )
    (net (code "42") (name "/GPIO21") (class "Default")
      (node (ref "J2") (pin "19") (pinfunction "19_19") (pintype "passive"))
      (node (ref "U1") (pin "25") (pinfunction "GPIO21/RTC_GPIO21_25") (pintype "passive"))
    )
    (net (code "43") (name "/GPIO26") (class "Default")
      (node (ref "J2") (pin "18") (pinfunction "18_18") (pintype "passive"))
      (node (ref "U1") (pin "26") (pinfunction "GPIO26/SPICS1_26") (pintype "passive"))
    )
    (net (code "44") (name "/GPIO33") (class "Default")
      (node (ref "J2") (pin "17") (pinfunction "17_17") (pintype "passive"))
      (node (ref "U1") (pin "28") (pinfunction "GPIO33/SPIIO4/FSPIHD/SUBSPIHD_28") (pintype "passive"))
    )
    (net (code "45") (name "/GPIO34") (class "Default")
      (node (ref "J2") (pin "16") (pinfunction "16_16") (pintype "passive"))
      (node (ref "U1") (pin "29") (pinfunction "GPIO34/SPIIO5/FSPICS0/SUBSPICS0_29") (pintype "passive"))
    )
    (net (code "46") (name "/GPIO35") (class "Default")
      (node (ref "J2") (pin "15") (pinfunction "15_15") (pintype "passive"))
      (node (ref "U1") (pin "31") (pinfunction "GPIO35/SPIIO6/FSPID/SUBSPID_31") (pintype "passive"))
    )
    (net (code "47") (name "/GPIO36") (class "Default")
      (node (ref "J2") (pin "14") (pinfunction "14_14") (pintype "passive"))
      (node (ref "U1") (pin "32") (pinfunction "GPIO36/SPIIO7/FSPICLK/SUBSPICLK_32") (pintype "passive"))
    )
    (net (code "48") (name "/GPIO37") (class "Default")
      (node (ref "J2") (pin "13") (pinfunction "13_13") (pintype "passive"))
      (node (ref "U1") (pin "33") (pinfunction "GPIO37/SPIDQS/FSPIQ/SUBSPIQ_33") (pintype "passive"))
    )
    (net (code "49") (name "/GPIO38") (class "Default")
      (node (ref "J2") (pin "12") (pinfunction "12_12") (pintype "passive"))
      (node (ref "U1") (pin "34") (pinfunction "GPIO38/FSPIWP/SUBSPIWP_34") (pintype "passive"))
    )
    (net (code "50") (name "/GPIO39") (class "Default")
      (node (ref "J2") (pin "11") (pinfunction "11_11") (pintype "passive"))
      (node (ref "U1") (pin "35") (pinfunction "MTCK/GPIO39/CLK_OUT3/SUBSPICS1_35") (pintype "passive"))
    )
    (net (code "51") (name "/GPIO40") (class "Default")
      (node (ref "J2") (pin "10") (pinfunction "10_10") (pintype "passive"))
      (node (ref "U1") (pin "36") (pinfunction "MTDO/GPIO40/CLK_OUT2_36") (pintype "passive"))
    )
    (net (code "52") (name "/GPIO41") (class "Default")
      (node (ref "J2") (pin "9") (pinfunction "9_9") (pintype "passive"))
      (node (ref "U1") (pin "37") (pinfunction "MTDI/GPIO41/CLK_OUT1_37") (pintype "passive"))
    )
    (net (code "53") (name "/GPIO42") (class "Default")
      (node (ref "J2") (pin "8") (pinfunction "8_8") (pintype "passive"))
      (node (ref "U1") (pin "38") (pinfunction "MTMS/GPIO42_38") (pintype "passive"))
    )
    (net (code "54") (name "/GPIO45") (class "Default")
      (node (ref "J2") (pin "5") (pinfunction "5_5") (pintype "passive"))
      (node (ref "U1") (pin "41") (pinfunction "GPIO45_41") (pintype "passive"))
    )
    (net (code "55") (name "/GPIO46") (class "Default")
      (node (ref "J2") (pin "4") (pinfunction "4_4") (pintype "passive"))
      (node (ref "U1") (pin "44") (pinfunction "GPIO46_44") (pintype "passive"))
    )
    (net (code "56") (name "/GPIO47") (class "Default")
      (node (ref "J2") (pin "23") (pinfunction "23_23") (pintype "passive"))
      (node (ref "U1") (pin "27") (pinfunction "GPIO47/SPICLK_P_DIFF/SUBSPICLK_P_DIFF_27") (pintype "passive"))
    )
    (net (code "57") (name "/GPIO48") (class "Default")
      (node (ref "J2") (pin "22") (pinfunction "22_22") (pintype "passive"))
      (node (ref "U1") (pin "30") (pinfunction "GPIO48/SPICLK_N_DIFF/SUBSPICLK_N_DIFF_30") (pintype "passive"))
    )
    (net (code "58") (name "/RTS_FTDI") (class "Default")
      (node (ref "Q1") (pin "2") (pinfunction "E_2") (pintype "passive"))
      (node (ref "R18") (pin "2") (pinfunction "2_2") (pintype "passive"))
      (node (ref "U2") (pin "19") (pinfunction "~{RTS}_19") (pintype "passive"))
    )
    (net (code "59") (name "/RXD_FTDI") (class "Default")
      (node (ref "R19") (pin "2") (pinfunction "2_2") (pintype "passive"))
      (node (ref "U2") (pin "1") (pinfunction "RXD_1") (pintype "passive"))
    )
    (net (code "60") (name "/TXD_FTDI") (class "Default")
      (node (ref "R20") (pin "2") (pinfunction "2_2") (pintype "passive"))
      (node (ref "U2") (pin "17") (pinfunction "TXD_17") (pintype "passive"))
    )
    (net (code "61") (name "/U0RXD") (class "Default")
      (node (ref "J2") (pin "6") (pinfunction "6_6") (pintype "passive"))
      (node (ref "R20") (pin "1") (pinfunction "1_1") (pintype "passive"))
      (node (ref "U1") (pin "40") (pinfunction "U0RXD/GPIO44/CLK_OUT2_40") (pintype "passive"))
    )
    (net (code "62") (name "/U0TXD") (class "Default")
      (node (ref "J2") (pin "7") (pinfunction "7_7") (pintype "passive"))
      (node (ref "R19") (pin "1") (pinfunction "1_1") (pintype "passive"))
      (node (ref "U1") (pin "39") (pinfunction "U0TXD/GPIO43/CLK_OUT1_39") (pintype "passive"))
    )
    (net (code "63") (name "/VBUS_SENSE") (class "Default")
      (node (ref "R10") (pin "1") (pinfunction "1_1") (pintype "passive"))
      (node (ref "R13") (pin "2") (pinfunction "2_2") (pintype "passive"))
      (node (ref "U2") (pin "16") (pinfunction "CBUS3_16") (pintype "passive"))
    )
    (net (code "64") (name "GND") (class "Default")
      (node (ref "C1") (pin "1") (pinfunction "1_1") (pintype "passive"))
      (node (ref "C10") (pin "2") (pinfunction "2_2") (pintype "passive"))
      (node (ref "C11") (pin "1") (pinfunction "1_1") (pintype "passive"))
      (node (ref "C12") (pin "1") (pinfunction "1_1") (pintype "passive"))
      (node (ref "C13") (pin "1") (pinfunction "1_1") (pintype "passive"))
      (node (ref "C14") (pin "1") (pinfunction "1_1") (pintype "passive"))
      (node (ref "C15") (pin "1") (pinfunction "1_1") (pintype "passive"))
      (node (ref "C16") (pin "1") (pinfunction "1_1") (pintype "passive"))
      (node (ref "C17") (pin "1") (pinfunction "1_1") (pintype "passive"))
      (node (ref "C2") (pin "1") (pinfunction "1_1") (pintype "passive"))
      (node (ref "C3") (pin "1") (pinfunction "1_1") (pintype "passive"))
      (node (ref "C4") (pin "2") (pinfunction "2_2") (pintype "passive"))
      (node (ref "C5") (pin "1") (pinfunction "1_1") (pintype "passive"))
      (node (ref "C6") (pin "1") (pinfunction "1_1") (pintype "passive"))
      (node (ref "C7") (pin "1") (pinfunction "1_1") (pintype "passive"))
      (node (ref "C8") (pin "1") (pinfunction "1_1") (pintype "passive"))
      (node (ref "C9") (pin "1") (pinfunction "1_1") (pintype "passive"))
      (node (ref "D1") (pin "1") (pinfunction "1_1") (pintype "passive"))
      (node (ref "D3") (pin "1") (pinfunction "1_1") (pintype "passive"))
      (node (ref "D4") (pin "1") (pinfunction "1_1") (pintype "passive"))
      (node (ref "D5") (pin "2") (pinfunction "2_2") (pintype "passive"))
      (node (ref "D6") (pin "1") (pinfunction "1_1") (pintype "passive"))
      (node (ref "D7") (pin "1") (pinfunction "1_1") (pintype "passive"))
      (node (ref "D8") (pin "2") (pinfunction "2_2") (pintype "passive"))
      (node (ref "J1") (pin "1") (pinfunction "1_1") (pintype "passive"))
      (node (ref "J1") (pin "23") (pinfunction "23_23") (pintype "passive"))
      (node (ref "J2") (pin "2") (pinfunction "2_2") (pintype "passive"))
      (node (ref "J2") (pin "24") (pinfunction "24_24") (pintype "passive"))
      (node (ref "J3") (pin "A1B12") (pinfunction "GND_A1B12_A1B12") (pintype "passive"))
      (node (ref "J3") (pin "B1A12") (pinfunction "GND_B1A12_B1A12") (pintype "passive"))
      (node (ref "J3") (pin "S1") (pinfunction "SHIELD_1_S1") (pintype "passive"))
      (node (ref "J3") (pin "S2") (pinfunction "SHIELD_2_S2") (pintype "passive"))
      (node (ref "J3") (pin "S3") (pinfunction "SHIELD_3_S3") (pintype "passive"))
      (node (ref "J3") (pin "S4") (pinfunction "SHIELD_4_S4") (pintype "passive"))
      (node (ref "J4") (pin "A1B12") (pinfunction "GND_A1B12_A1B12") (pintype "passive"))
      (node (ref "J4") (pin "B1A12") (pinfunction "GND_B1A12_B1A12") (pintype "passive"))
      (node (ref "J4") (pin "S1") (pinfunction "SHIELD_1_S1") (pintype "passive"))
      (node (ref "J4") (pin "S2") (pinfunction "SHIELD_2_S2") (pintype "passive"))
      (node (ref "J4") (pin "S3") (pinfunction "SHIELD_3_S3") (pintype "passive"))
      (node (ref "J4") (pin "S4") (pinfunction "SHIELD_4_S4") (pintype "passive"))
      (node (ref "R11") (pin "1") (pinfunction "1_1") (pintype "passive"))
      (node (ref "R12") (pin "1") (pinfunction "1_1") (pintype "passive"))
      (node (ref "R13") (pin "1") (pinfunction "1_1") (pintype "passive"))
      (node (ref "R14") (pin "1") (pinfunction "1_1") (pintype "passive"))
      (node (ref "R15") (pin "1") (pinfunction "1_1") (pintype "passive"))
      (node (ref "R9") (pin "2") (pinfunction "2_2") (pintype "passive"))
      (node (ref "SW1") (pin "3") (pinfunction "3_3") (pintype "passive"))
      (node (ref "SW1") (pin "4") (pinfunction "4_4") (pintype "passive"))
      (node (ref "SW2") (pin "3") (pinfunction "3_3") (pintype "passive"))
      (node (ref "SW2") (pin "4") (pinfunction "4_4") (pintype "passive"))
      (node (ref "U1") (pin "1") (pinfunction "GND_1_1") (pintype "passive"))
      (node (ref "U1") (pin "2") (pinfunction "GND_2_2") (pintype "passive"))
      (node (ref "U1") (pin "42") (pinfunction "GND_42") (pintype "passive"))
      (node (ref "U1") (pin "43") (pinfunction "GND_43") (pintype "passive"))
      (node (ref "U1") (pin "46") (pinfunction "GND_46_46") (pintype "passive"))
      (node (ref "U1") (pin "47") (pinfunction "GND_47_47") (pintype "passive"))
      (node (ref "U1") (pin "48") (pinfunction "GND_48_48") (pintype "passive"))
      (node (ref "U1") (pin "49") (pinfunction "GND_49_49") (pintype "passive"))
      (node (ref "U1") (pin "50") (pinfunction "GND_50_50") (pintype "passive"))
      (node (ref "U1") (pin "51") (pinfunction "GND_51_51") (pintype "passive"))
      (node (ref "U1") (pin "52") (pinfunction "GND_52_52") (pintype "passive"))
      (node (ref "U1") (pin "53") (pinfunction "GND_53_53") (pintype "passive"))
      (node (ref "U1") (pin "54") (pinfunction "GND_54_54") (pintype "passive"))
      (node (ref "U1") (pin "55") (pinfunction "GND_55_55") (pintype "passive"))
      (node (ref "U1") (pin "56") (pinfunction "GND_56_56") (pintype "passive"))
      (node (ref "U1") (pin "57") (pinfunction "GND_57_57") (pintype "passive"))
      (node (ref "U1") (pin "58") (pinfunction "GND_58_58") (pintype "passive"))
      (node (ref "U1") (pin "59") (pinfunction "GND_59_59") (pintype "passive"))
      (node (ref "U1") (pin "60") (pinfunction "GND_60_60") (pintype "passive"))
      (node (ref "U1") (pin "61") (pinfunction "GND_61_61") (pintype "passive"))
      (node (ref "U1") (pin "62") (pinfunction "GND_62_62") (pintype "passive"))
      (node (ref "U1") (pin "63") (pinfunction "GND_63_63") (pintype "passive"))
      (node (ref "U1") (pin "64") (pinfunction "GND_64_64") (pintype "passive"))
      (node (ref "U1") (pin "65") (pinfunction "GND_65_65") (pintype "passive"))
      (node (ref "U1") (pin "66") (pinfunction "GND_66_66") (pintype "passive"))
      (node (ref "U1") (pin "67") (pinfunction "GND_67_67") (pintype "passive"))
      (node (ref "U1") (pin "68") (pinfunction "GND_68_68") (pintype "passive"))
      (node (ref "U1") (pin "69") (pinfunction "GND_69_69") (pintype "passive"))
      (node (ref "U1") (pin "70") (pinfunction "GND_70_70") (pintype "passive"))
      (node (ref "U1") (pin "71") (pinfunction "GND_71_71") (pintype "passive"))
      (node (ref "U1") (pin "72") (pinfunction "GND_72_72") (pintype "passive"))
      (node (ref "U1") (pin "73") (pinfunction "GND_73_73") (pintype "passive"))
      (node (ref "U2") (pin "13") (pinfunction "GND_13") (pintype "passive"))
      (node (ref "U2") (pin "21") (pinfunction "GND_21") (pintype "passive"))
      (node (ref "U2") (pin "3") (pinfunction "GND_3") (pintype "passive"))
      (node (ref "U3") (pin "2") (pinfunction "GND_2") (pintype "power_in"))
      (node (ref "U3") (pin "4") (pinfunction "GND_4") (pintype "power_in"))
    )
    (net (code "65") (name "Net-(D1-Pad2)") (class "Default")
      (node (ref "D1") (pin "2") (pinfunction "2_2") (pintype "passive"))
      (node (ref "R5") (pin "1") (pinfunction "1_1") (pintype "passive"))
    )
    (net (code "66") (name "Net-(D2-Pad2)") (class "Default")
      (node (ref "D2") (pin "2") (pinfunction "2_2") (pintype "passive"))
      (node (ref "R6") (pin "1") (pinfunction "1_1") (pintype "passive"))
    )
    (net (code "67") (name "Net-(J3-CC1)") (class "Default")
      (node (ref "J3") (pin "A5") (pinfunction "CC1_A5") (pintype "passive"))
      (node (ref "R12") (pin "2") (pinfunction "2_2") (pintype "passive"))
    )
    (net (code "68") (name "Net-(J3-CC2)") (class "Default")
      (node (ref "J3") (pin "B5") (pinfunction "CC2_B5") (pintype "passive"))
      (node (ref "R11") (pin "2") (pinfunction "2_2") (pintype "passive"))
    )
    (net (code "69") (name "Net-(J4-CC1)") (class "Default")
      (node (ref "J4") (pin "A5") (pinfunction "CC1_A5") (pintype "passive"))
      (node (ref "R15") (pin "2") (pinfunction "2_2") (pintype "passive"))
    )
    (net (code "70") (name "Net-(J4-CC2)") (class "Default")
      (node (ref "J4") (pin "B5") (pinfunction "CC2_B5") (pintype "passive"))
      (node (ref "R14") (pin "2") (pinfunction "2_2") (pintype "passive"))
    )
    (net (code "71") (name "Net-(Q1-B)") (class "Default")
      (node (ref "Q1") (pin "1") (pinfunction "B_1") (pintype "passive"))
      (node (ref "R16") (pin "1") (pinfunction "1_1") (pintype "passive"))
    )
    (net (code "72") (name "Net-(Q2-B)") (class "Default")
      (node (ref "Q2") (pin "1") (pinfunction "B_1") (pintype "passive"))
      (node (ref "R18") (pin "1") (pinfunction "1_1") (pintype "passive"))
    )
    (net (code "73") (name "Net-(U2-CBUS0)") (class "Default")
      (node (ref "R9") (pin "1") (pinfunction "1_1") (pintype "passive"))
      (node (ref "U2") (pin "15") (pinfunction "CBUS0_15") (pintype "passive"))
    )
    (net (code "74") (name "unconnected-(J1-Pad24)") (class "Default")
      (node (ref "J1") (pin "24") (pinfunction "24_24") (pintype "passive+no_connect"))
    )
    (net (code "75") (name "unconnected-(J3-SBU1-PadA8)") (class "Default")
      (node (ref "J3") (pin "A8") (pinfunction "SBU1_A8") (pintype "passive+no_connect"))
    )
    (net (code "76") (name "unconnected-(J3-SBU2-PadB8)") (class "Default")
      (node (ref "J3") (pin "B8") (pinfunction "SBU2_B8") (pintype "passive+no_connect"))
    )
    (net (code "77") (name "unconnected-(J4-SBU1-PadA8)") (class "Default")
      (node (ref "J4") (pin "A8") (pinfunction "SBU1_A8") (pintype "passive+no_connect"))
    )
    (net (code "78") (name "unconnected-(J4-SBU2-PadB8)") (class "Default")
      (node (ref "J4") (pin "B8") (pinfunction "SBU2_B8") (pintype "passive+no_connect"))
    )
    (net (code "79") (name "unconnected-(U2-CBUS1-Pad14)") (class "Default")
      (node (ref "U2") (pin "14") (pinfunction "CBUS1_14") (pintype "passive+no_connect"))
    )
    (net (code "80") (name "unconnected-(U2-CBUS2-Pad7)") (class "Default")
      (node (ref "U2") (pin "7") (pinfunction "CBUS2_7") (pintype "passive+no_connect"))
    )
    (net (code "81") (name "unconnected-(U2-~{CTS}-Pad6)") (class "Default")
      (node (ref "U2") (pin "6") (pinfunction "~{CTS}_6") (pintype "passive+no_connect"))
    )
    (net (code "82") (name "unconnected-(U2-~{DCD}-Pad5)") (class "Default")
      (node (ref "U2") (pin "5") (pinfunction "~{DCD}_5") (pintype "passive+no_connect"))
    )
    (net (code "83") (name "unconnected-(U2-~{DSR}-Pad4)") (class "Default")
      (node (ref "U2") (pin "4") (pinfunction "~{DSR}_4") (pintype "passive+no_connect"))
    )
    (net (code "84") (name "unconnected-(U2-~{RI}-Pad2)") (class "Default")
      (node (ref "U2") (pin "2") (pinfunction "~{RI}_2") (pintype "passive+no_connect"))
    )
  )
)
